# Subtractor.net
KiCad netlist of a schematic drawn in Altium Designer
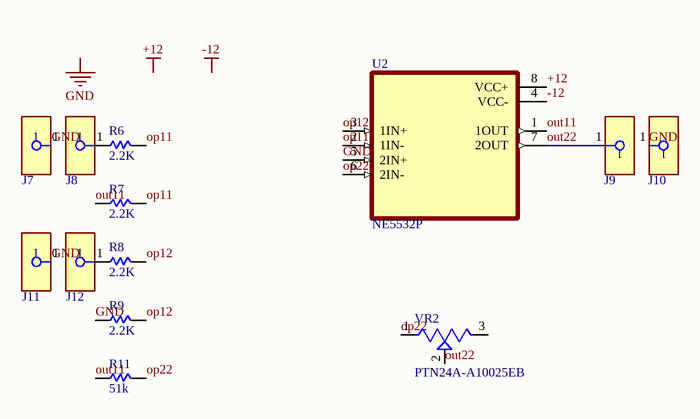
[diagram p0: Subtractor.SchDoc]

(export (version "E")
  (design (tool "Eeschema 10.0.6"))
  (components
    (comp (ref "J7")
      (value "1581-5")
      (footprint "FP-1581-5-MFG")
      (description "CONN BANANA JACK TURRET GREEN")
      (libsource (lib "Schlib1") (part "CMP-73906-000011-1"))
    )
    (comp (ref "J8")
      (value "1581-5")
      (footprint "FP-1581-5-MFG")
      (description "CONN BANANA JACK TURRET GREEN")
      (libsource (lib "Schlib1") (part "CMP-73906-000011-1"))
    )
    (comp (ref "J9")
      (value "1581-5")
      (footprint "FP-1581-5-MFG")
      (description "CONN BANANA JACK TURRET GREEN")
      (libsource (lib "") (part "CMP-73906-000011-1_1"))
    )
    (comp (ref "J10")
      (value "1581-5")
      (footprint "FP-1581-5-MFG")
      (description "CONN BANANA JACK TURRET GREEN")
      (libsource (lib "") (part "CMP-73906-000011-1_1"))
    )
    (comp (ref "J11")
      (value "1581-5")
      (footprint "FP-1581-5-MFG")
      (description "CONN BANANA JACK TURRET GREEN")
      (libsource (lib "Schlib1") (part "CMP-73906-000011-1"))
    )
    (comp (ref "J12")
      (value "1581-5")
      (footprint "FP-1581-5-MFG")
      (description "CONN BANANA JACK TURRET GREEN")
      (libsource (lib "Schlib1") (part "CMP-73906-000011-1"))
    )
    (comp (ref "R6")
      (value "2.2K")
      (footprint "RESAD1100W55L680D260")
      (description "1.07 kOhms Â±1% 0.25W, 1/4W Through Hole Resistor Axial - Metal Film")
      (fields (field (name "MF") "Yageo") (field (name "MP") "MFR-25FBF52-1K"))
      (libsource (lib "Schlib1") (part "MFR-25FBF52-1K"))
    )
    (comp (ref "R7")
      (value "2.2K")
      (footprint "RESAD1100W55L680D260")
      (description "1.07 kOhms Â±1% 0.25W, 1/4W Through Hole Resistor Axial - Metal Film")
      (fields (field (name "MF") "Yageo") (field (name "MP") "MFR-25FBF52-1K"))
      (libsource (lib "Schlib1") (part "MFR-25FBF52-1K"))
    )
    (comp (ref "R8")
      (value "2.2K")
      (footprint "RESAD1100W55L680D260")
      (description "1.07 kOhms Â±1% 0.25W, 1/4W Through Hole Resistor Axial - Metal Film")
      (fields (field (name "MF") "Yageo") (field (name "MP") "MFR-25FBF52-1K"))
      (libsource (lib "Schlib1") (part "MFR-25FBF52-1K"))
    )
    (comp (ref "R9")
      (value "2.2K")
      (footprint "RESAD1100W55L680D260")
      (description "1.07 kOhms Â±1% 0.25W, 1/4W Through Hole Resistor Axial - Metal Film")
      (fields (field (name "MF") "Yageo") (field (name "MP") "MFR-25FBF52-1K"))
      (libsource (lib "Schlib1") (part "MFR-25FBF52-1K"))
    )
    (comp (ref "R11")
      (value "51k")
      (footprint "RESAD1100W55L680D260")
      (description "1.07 kOhms Â±1% 0.25W, 1/4W Through Hole Resistor Axial - Metal Film")
      (fields (field (name "MF") "Yageo") (field (name "MP") "MFR-25FBF52-1K"))
      (libsource (lib "Schlib1") (part "MFR-25FBF52-1K"))
    )
    (comp (ref "U2")
      (value "NE5532P")
      (footprint "DIP794W45P254L959H508Q8")
      (description "Dual, 30-V, 10-MHz, low-noise operational amplifier for audio applications")
      (fields (field (name "MF") "Texas Instruments"))
      (libsource (lib "Schlib1") (part "NE5532P"))
    )
    (comp (ref "VR2")
      (value "PTN24A-A10025EB")
      (footprint "TRIM_PTN24A-A10025EB")
      (description "100k Ohm 1 Gang Linear Panel Mount Potentiometer 1.0 Turns Carbon 0.5W, 1/2W PC Pins")
      (fields (field (name "MF") "Same Sky"))
      (libsource (lib "Schlib1") (part "PTN24A-A10025EB"))
    )
  )
  (nets
    (net (code "1") (name "+12") (class "Default")
      (node (ref "U2") (pin "8") (pinfunction "VCC+_8") (pintype "power_in"))
    )
    (net (code "2") (name "-12") (class "Default")
      (node (ref "U2") (pin "4") (pinfunction "VCC-_4") (pintype "power_in"))
    )
    (net (code "3") (name "/op11") (class "Default")
      (node (ref "R6") (pin "2") (pinfunction "2_2") (pintype "passive"))
      (node (ref "R7") (pin "2") (pinfunction "2_2") (pintype "passive"))
      (node (ref "U2") (pin "2") (pinfunction "1IN-_2") (pintype "input"))
    )
    (net (code "4") (name "/op12") (class "Default")
      (node (ref "R8") (pin "2") (pinfunction "2_2") (pintype "passive"))
      (node (ref "R9") (pin "2") (pinfunction "2_2") (pintype "passive"))
      (node (ref "U2") (pin "3") (pinfunction "1IN+_3") (pintype "input"))
    )
    (net (code "5") (name "/op22") (class "Default")
      (node (ref "R11") (pin "2") (pinfunction "2_2") (pintype "passive"))
      (node (ref "U2") (pin "6") (pinfunction "2IN-_6") (pintype "input"))
      (node (ref "VR2") (pin "1") (pinfunction "1_1") (pintype "passive"))
    )
    (net (code "6") (name "/out11") (class "Default")
      (node (ref "R11") (pin "1") (pinfunction "1_1") (pintype "passive"))
      (node (ref "R7") (pin "1") (pinfunction "1_1") (pintype "passive"))
      (node (ref "U2") (pin "1") (pinfunction "1OUT_1") (pintype "output"))
    )
    (net (code "7") (name "/out22") (class "Default")
      (node (ref "J9") (pin "1") (pinfunction "1_1") (pintype "passive"))
      (node (ref "U2") (pin "7") (pinfunction "2OUT_7") (pintype "output"))
      (node (ref "VR2") (pin "2") (pinfunction "2_2") (pintype "passive"))
    )
    (net (code "8") (name "GND") (class "Default")
      (node (ref "J10") (pin "1") (pinfunction "1_1") (pintype "passive"))
      (node (ref "J11") (pin "1") (pinfunction "1_1") (pintype "passive"))
      (node (ref "J7") (pin "1") (pinfunction "1_1") (pintype "passive"))
      (node (ref "R9") (pin "1") (pinfunction "1_1") (pintype "passive"))
      (node (ref "U2") (pin "5") (pinfunction "2IN+_5") (pintype "input"))
    )
    (net (code "9") (name "Net-(J8-Pad1)") (class "Default")
      (node (ref "J8") (pin "1") (pinfunction "1_1") (pintype "passive"))
      (node (ref "R6") (pin "1") (pinfunction "1_1") (pintype "passive"))
    )
    (net (code "10") (name "Net-(J12-Pad1)") (class "Default")
      (node (ref "J12") (pin "1") (pinfunction "1_1") (pintype "passive"))
      (node (ref "R8") (pin "1") (pinfunction "1_1") (pintype "passive"))
    )
    (net (code "11") (name "unconnected-(VR2-Pad3)") (class "Default")
      (node (ref "VR2") (pin "3") (pinfunction "3_3") (pintype "passive"))
    )
  )
)
